# stm32f4discovery-daugherboard-v1.net
KiCad netlist of a schematic drawn in EAGLE
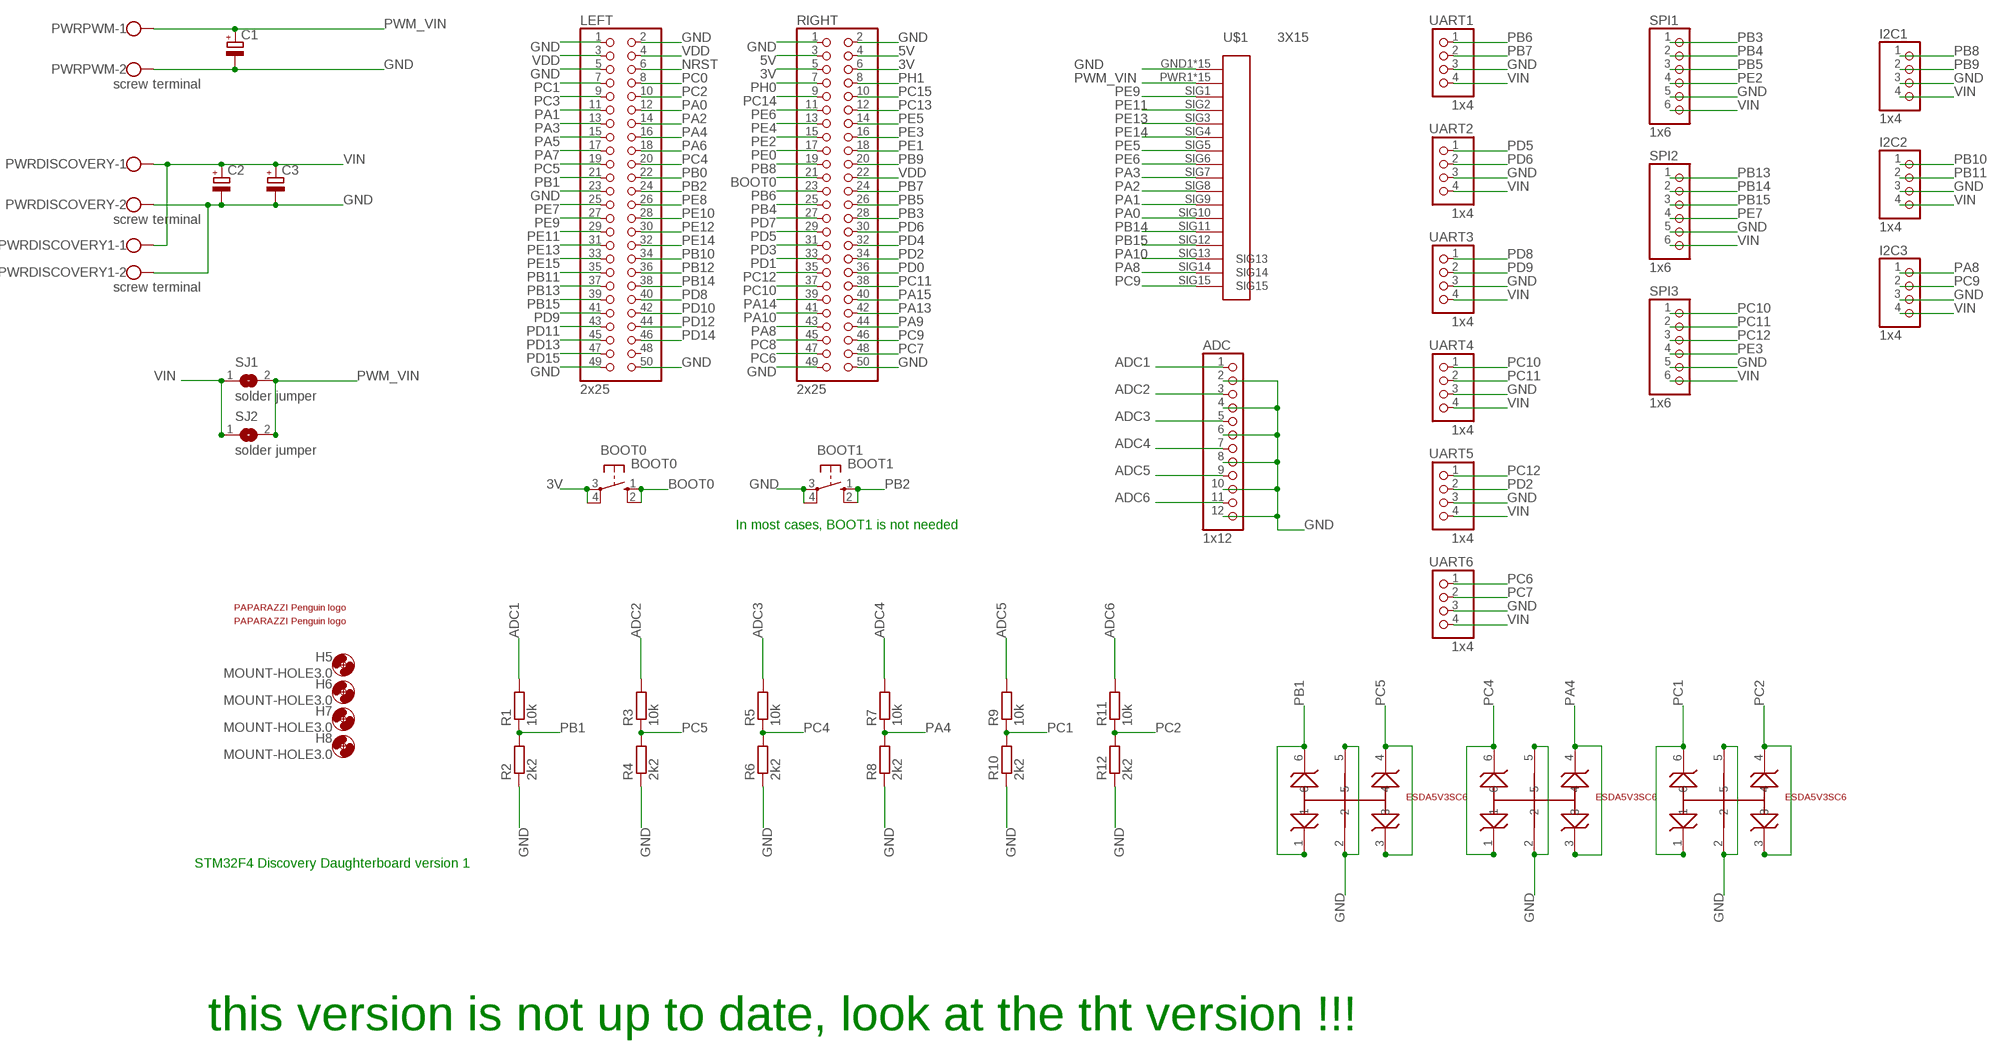
[diagram p0: schematic, sheet 1]

(export (version "E")
  (design (tool "Eeschema 10.0.6"))
  (components
    (comp (ref "ADC")
      (value "1x12")
      (footprint "eagle-import:1X12_90")
      (libsource (lib "eagle-import") (part "PINHD-1X12/90"))
    )
    (comp (ref "BOOT0")
      (value "BOOT0")
      (footprint "eagle-import:B3F-10XX")
      (fields (field (name "MPN") "B3F-1000"))
      (libsource (lib "eagle-import") (part "10-XX"))
    )
    (comp (ref "BOOT1")
      (value "BOOT1")
      (footprint "eagle-import:B3F-10XX")
      (fields (field (name "MPN") "B3F-1000"))
      (libsource (lib "eagle-import") (part "10-XX"))
    )
    (comp (ref "C1")
      (value "CPOL-EU153CLV-0807")
      (footprint "eagle-import:153CLV-0807")
      (libsource (lib "eagle-import") (part "CPOL-EU153CLV-0807"))
    )
    (comp (ref "C2")
      (value "CPOL-EU153CLV-0807")
      (footprint "eagle-import:153CLV-0807")
      (libsource (lib "eagle-import") (part "CPOL-EU153CLV-0807"))
    )
    (comp (ref "C3")
      (value "CPOL-EU153CLV-0807")
      (footprint "eagle-import:153CLV-0807")
      (libsource (lib "eagle-import") (part "CPOL-EU153CLV-0807"))
    )
    (comp (ref "H5")
      (value "MOUNT-HOLE3.0")
      (footprint "eagle-import:3,0")
      (libsource (lib "eagle-import") (part "MOUNT-HOLE3.0"))
    )
    (comp (ref "H6")
      (value "MOUNT-HOLE3.0")
      (footprint "eagle-import:3,0")
      (libsource (lib "eagle-import") (part "MOUNT-HOLE3.0"))
    )
    (comp (ref "H7")
      (value "MOUNT-HOLE3.0")
      (footprint "eagle-import:3,0")
      (libsource (lib "eagle-import") (part "MOUNT-HOLE3.0"))
    )
    (comp (ref "H8")
      (value "MOUNT-HOLE3.0")
      (footprint "eagle-import:3,0")
      (libsource (lib "eagle-import") (part "MOUNT-HOLE3.0"))
    )
    (comp (ref "I2C1")
      (value "1x4")
      (footprint "eagle-import:1X04_90")
      (libsource (lib "eagle-import") (part "PINHD-1X4/90"))
    )
    (comp (ref "I2C2")
      (value "1x4")
      (footprint "eagle-import:1X04_90")
      (libsource (lib "eagle-import") (part "PINHD-1X4/90"))
    )
    (comp (ref "I2C3")
      (value "1x4")
      (footprint "eagle-import:1X04_90")
      (libsource (lib "eagle-import") (part "PINHD-1X4/90"))
    )
    (comp (ref "LEFT")
      (value "2x25")
      (footprint "eagle-import:2X25")
      (libsource (lib "eagle-import") (part "PINHD-2X25"))
    )
    (comp (ref "PWRDISCOVERY")
      (value "screw terminal")
      (footprint "eagle-import:W237-102")
      (fields (field (name "MPN") "237-102"))
      (libsource (lib "eagle-import") (part "W237-102"))
    )
    (comp (ref "PWRDISCOVERY1")
      (value "screw terminal")
      (footprint "eagle-import:W237-102")
      (fields
        (field (name "MPN") "237-102")
        (field (name "MPN_1") "237-102")
        (field (name "OC_FARNELL") "unknown")
        (field (name "OC_NEWARK") "70K9898")
      )
      (libsource (lib "eagle-import") (part "W237-102"))
    )
    (comp (ref "PWRPWM")
      (value "screw terminal")
      (footprint "eagle-import:W237-102")
      (fields (field (name "MPN") "237-102"))
      (libsource (lib "eagle-import") (part "W237-102"))
    )
    (comp (ref "R1")
      (value "10k")
      (footprint "eagle-import:R0805")
      (libsource (lib "eagle-import") (part "R-EU_R0805"))
    )
    (comp (ref "R2")
      (value "2k2")
      (footprint "eagle-import:R0805")
      (libsource (lib "eagle-import") (part "R-EU_R0805"))
    )
    (comp (ref "R3")
      (value "10k")
      (footprint "eagle-import:R0805")
      (libsource (lib "eagle-import") (part "R-EU_R0805"))
    )
    (comp (ref "R4")
      (value "2k2")
      (footprint "eagle-import:R0805")
      (libsource (lib "eagle-import") (part "R-EU_R0805"))
    )
    (comp (ref "R5")
      (value "10k")
      (footprint "eagle-import:R0805")
      (libsource (lib "eagle-import") (part "R-EU_R0805"))
    )
    (comp (ref "R6")
      (value "2k2")
      (footprint "eagle-import:R0805")
      (libsource (lib "eagle-import") (part "R-EU_R0805"))
    )
    (comp (ref "R7")
      (value "10k")
      (footprint "eagle-import:R0805")
      (libsource (lib "eagle-import") (part "R-EU_R0805"))
    )
    (comp (ref "R8")
      (value "2k2")
      (footprint "eagle-import:R0805")
      (libsource (lib "eagle-import") (part "R-EU_R0805"))
    )
    (comp (ref "R9")
      (value "10k")
      (footprint "eagle-import:R0805")
      (libsource (lib "eagle-import") (part "R-EU_R0805"))
    )
    (comp (ref "R10")
      (value "2k2")
      (footprint "eagle-import:R0805")
      (libsource (lib "eagle-import") (part "R-EU_R0805"))
    )
    (comp (ref "R11")
      (value "10k")
      (footprint "eagle-import:R0805")
      (libsource (lib "eagle-import") (part "R-EU_R0805"))
    )
    (comp (ref "R12")
      (value "2k2")
      (footprint "eagle-import:R0805")
      (libsource (lib "eagle-import") (part "R-EU_R0805"))
    )
    (comp (ref "RIGHT")
      (value "2x25")
      (footprint "eagle-import:2X25")
      (libsource (lib "eagle-import") (part "PINHD-2X25"))
    )
    (comp (ref "SJ1")
      (value "solder jumper")
      (footprint "eagle-import:SJW")
      (libsource (lib "eagle-import") (part "SJW"))
    )
    (comp (ref "SJ2")
      (value "solder jumper")
      (footprint "eagle-import:SJW")
      (libsource (lib "eagle-import") (part "SJW"))
    )
    (comp (ref "SPI1")
      (value "1x6")
      (footprint "eagle-import:1X06_90")
      (libsource (lib "eagle-import") (part "PINHD-1X6/90"))
    )
    (comp (ref "SPI2")
      (value "1x6")
      (footprint "eagle-import:1X06_90")
      (libsource (lib "eagle-import") (part "PINHD-1X6/90"))
    )
    (comp (ref "SPI3")
      (value "1x6")
      (footprint "eagle-import:1X06_90")
      (libsource (lib "eagle-import") (part "PINHD-1X6/90"))
    )
    (comp (ref "U$1")
      (value "3X15")
      (footprint "eagle-import:3X15")
      (libsource (lib "eagle-import") (part "3X15"))
    )
    (comp (ref "U$2")
      (value "PAPARAZZI")
      (footprint "eagle-import:PAPARAZZI")
      (libsource (lib "eagle-import") (part "PAPARAZZI"))
    )
    (comp (ref "U$3")
      (value "PAPARAZZI")
      (footprint "eagle-import:PAPARAZZI")
      (libsource (lib "eagle-import") (part "PAPARAZZI"))
    )
    (comp (ref "U$4")
      (value "ESDA5V3SC6")
      (footprint "eagle-import:SOT23-6")
      (libsource (lib "eagle-import") (part "ESDA5V3SC6"))
    )
    (comp (ref "U$5")
      (value "ESDA5V3SC6")
      (footprint "eagle-import:SOT23-6")
      (libsource (lib "eagle-import") (part "ESDA5V3SC6"))
    )
    (comp (ref "U$6")
      (value "ESDA5V3SC6")
      (footprint "eagle-import:SOT23-6")
      (libsource (lib "eagle-import") (part "ESDA5V3SC6"))
    )
    (comp (ref "UART1")
      (value "1x4")
      (footprint "eagle-import:1X04_90")
      (libsource (lib "eagle-import") (part "PINHD-1X4/90"))
    )
    (comp (ref "UART2")
      (value "1x4")
      (footprint "eagle-import:1X04_90")
      (libsource (lib "eagle-import") (part "PINHD-1X4/90"))
    )
    (comp (ref "UART3")
      (value "1x4")
      (footprint "eagle-import:1X04_90")
      (libsource (lib "eagle-import") (part "PINHD-1X4/90"))
    )
    (comp (ref "UART4")
      (value "1x4")
      (footprint "eagle-import:1X04_90")
      (libsource (lib "eagle-import") (part "PINHD-1X4/90"))
    )
    (comp (ref "UART5")
      (value "1x4")
      (footprint "eagle-import:1X04_90")
      (libsource (lib "eagle-import") (part "PINHD-1X4/90"))
    )
    (comp (ref "UART6")
      (value "1x4")
      (footprint "eagle-import:1X04_90")
      (libsource (lib "eagle-import") (part "PINHD-1X4/90"))
    )
  )
  (nets
    (net (code "1") (name "/3V") (class "Default")
      (node (ref "BOOT0") (pin "3") (pinfunction "P_3") (pintype "passive"))
      (node (ref "BOOT0") (pin "4") (pinfunction "P1_4") (pintype "passive"))
      (node (ref "RIGHT") (pin "5") (pinfunction "5_5") (pintype "passive"))
      (node (ref "RIGHT") (pin "6") (pinfunction "6_6") (pintype "passive"))
    )
    (net (code "2") (name "/5V") (class "Default")
      (node (ref "RIGHT") (pin "3") (pinfunction "3_3") (pintype "passive"))
      (node (ref "RIGHT") (pin "4") (pinfunction "4_4") (pintype "passive"))
    )
    (net (code "3") (name "/ADC1") (class "Default")
      (node (ref "ADC") (pin "1") (pinfunction "1_1") (pintype "passive"))
      (node (ref "R1") (pin "2") (pinfunction "2_2") (pintype "passive"))
    )
    (net (code "4") (name "/ADC2") (class "Default")
      (node (ref "ADC") (pin "3") (pinfunction "3_3") (pintype "passive"))
      (node (ref "R3") (pin "2") (pinfunction "2_2") (pintype "passive"))
    )
    (net (code "5") (name "/ADC3") (class "Default")
      (node (ref "ADC") (pin "5") (pinfunction "5_5") (pintype "passive"))
      (node (ref "R5") (pin "2") (pinfunction "2_2") (pintype "passive"))
    )
    (net (code "6") (name "/ADC4") (class "Default")
      (node (ref "ADC") (pin "7") (pinfunction "7_7") (pintype "passive"))
      (node (ref "R7") (pin "2") (pinfunction "2_2") (pintype "passive"))
    )
    (net (code "7") (name "/ADC5") (class "Default")
      (node (ref "ADC") (pin "9") (pinfunction "9_9") (pintype "passive"))
      (node (ref "R9") (pin "2") (pinfunction "2_2") (pintype "passive"))
    )
    (net (code "8") (name "/ADC6") (class "Default")
      (node (ref "ADC") (pin "11") (pinfunction "11_11") (pintype "passive"))
      (node (ref "R11") (pin "2") (pinfunction "2_2") (pintype "passive"))
    )
    (net (code "9") (name "/BOOT0") (class "Default")
      (node (ref "BOOT0") (pin "1") (pinfunction "S_1") (pintype "passive"))
      (node (ref "BOOT0") (pin "2") (pinfunction "S1_2") (pintype "passive"))
      (node (ref "RIGHT") (pin "21") (pinfunction "21_21") (pintype "passive"))
    )
    (net (code "10") (name "/GND") (class "Default")
      (node (ref "ADC") (pin "10") (pinfunction "10_10") (pintype "passive"))
      (node (ref "ADC") (pin "12") (pinfunction "12_12") (pintype "passive"))
      (node (ref "ADC") (pin "2") (pinfunction "2_2") (pintype "passive"))
      (node (ref "ADC") (pin "4") (pinfunction "4_4") (pintype "passive"))
      (node (ref "ADC") (pin "6") (pinfunction "6_6") (pintype "passive"))
      (node (ref "ADC") (pin "8") (pinfunction "8_8") (pintype "passive"))
      (node (ref "BOOT1") (pin "3") (pinfunction "P_3") (pintype "passive"))
      (node (ref "BOOT1") (pin "4") (pinfunction "P1_4") (pintype "passive"))
      (node (ref "C1") (pin "-") (pinfunction "-_-") (pintype "passive"))
      (node (ref "C2") (pin "-") (pinfunction "-_-") (pintype "passive"))
      (node (ref "C3") (pin "-") (pinfunction "-_-") (pintype "passive"))
      (node (ref "I2C1") (pin "3") (pinfunction "3_3") (pintype "passive"))
      (node (ref "I2C2") (pin "3") (pinfunction "3_3") (pintype "passive"))
      (node (ref "I2C3") (pin "3") (pinfunction "3_3") (pintype "passive"))
      (node (ref "LEFT") (pin "1") (pinfunction "1_1") (pintype "passive"))
      (node (ref "LEFT") (pin "2") (pinfunction "2_2") (pintype "passive"))
      (node (ref "LEFT") (pin "23") (pinfunction "23_23") (pintype "passive"))
      (node (ref "LEFT") (pin "49") (pinfunction "49_49") (pintype "passive"))
      (node (ref "LEFT") (pin "5") (pinfunction "5_5") (pintype "passive"))
      (node (ref "LEFT") (pin "50") (pinfunction "50_50") (pintype "passive"))
      (node (ref "PWRDISCOVERY") (pin "2") (pinfunction "KL_2") (pintype "passive"))
      (node (ref "PWRDISCOVERY1") (pin "2") (pinfunction "KL_2") (pintype "passive"))
      (node (ref "PWRPWM") (pin "2") (pinfunction "KL_2") (pintype "passive"))
      (node (ref "R10") (pin "1") (pinfunction "1_1") (pintype "passive"))
      (node (ref "R12") (pin "1") (pinfunction "1_1") (pintype "passive"))
      (node (ref "R2") (pin "1") (pinfunction "1_1") (pintype "passive"))
      (node (ref "R4") (pin "1") (pinfunction "1_1") (pintype "passive"))
      (node (ref "R6") (pin "1") (pinfunction "1_1") (pintype "passive"))
      (node (ref "R8") (pin "1") (pinfunction "1_1") (pintype "passive"))
      (node (ref "RIGHT") (pin "1") (pinfunction "1_1") (pintype "passive"))
      (node (ref "RIGHT") (pin "2") (pinfunction "2_2") (pintype "passive"))
      (node (ref "RIGHT") (pin "49") (pinfunction "49_49") (pintype "passive"))
      (node (ref "RIGHT") (pin "50") (pinfunction "50_50") (pintype "passive"))
      (node (ref "SPI1") (pin "5") (pinfunction "5_5") (pintype "passive"))
      (node (ref "SPI2") (pin "5") (pinfunction "5_5") (pintype "passive"))
      (node (ref "SPI3") (pin "5") (pinfunction "5_5") (pintype "passive"))
      (node (ref "U$1") (pin "GND1") (pinfunction "GND_GND1") (pintype "bidirectional"))
      (node (ref "U$1") (pin "GND10") (pinfunction "GND_GND10") (pintype "bidirectional"))
      (node (ref "U$1") (pin "GND11") (pinfunction "GND_GND11") (pintype "bidirectional"))
      (node (ref "U$1") (pin "GND12") (pinfunction "GND_GND12") (pintype "bidirectional"))
      (node (ref "U$1") (pin "GND13") (pinfunction "GND_GND13") (pintype "bidirectional"))
      (node (ref "U$1") (pin "GND14") (pinfunction "GND_GND14") (pintype "bidirectional"))
      (node (ref "U$1") (pin "GND15") (pinfunction "GND_GND15") (pintype "bidirectional"))
      (node (ref "U$1") (pin "GND2") (pinfunction "GND_GND2") (pintype "bidirectional"))
      (node (ref "U$1") (pin "GND3") (pinfunction "GND_GND3") (pintype "bidirectional"))
      (node (ref "U$1") (pin "GND4") (pinfunction "GND_GND4") (pintype "bidirectional"))
      (node (ref "U$1") (pin "GND5") (pinfunction "GND_GND5") (pintype "bidirectional"))
      (node (ref "U$1") (pin "GND6") (pinfunction "GND_GND6") (pintype "bidirectional"))
      (node (ref "U$1") (pin "GND7") (pinfunction "GND_GND7") (pintype "bidirectional"))
      (node (ref "U$1") (pin "GND8") (pinfunction "GND_GND8") (pintype "bidirectional"))
      (node (ref "U$1") (pin "GND9") (pinfunction "GND_GND9") (pintype "bidirectional"))
      (node (ref "U$4") (pin "2") (pinfunction "2_2") (pintype "bidirectional"))
      (node (ref "U$4") (pin "5") (pinfunction "5_5") (pintype "bidirectional"))
      (node (ref "U$5") (pin "2") (pinfunction "2_2") (pintype "bidirectional"))
      (node (ref "U$5") (pin "5") (pinfunction "5_5") (pintype "bidirectional"))
      (node (ref "U$6") (pin "2") (pinfunction "2_2") (pintype "bidirectional"))
      (node (ref "U$6") (pin "5") (pinfunction "5_5") (pintype "bidirectional"))
      (node (ref "UART1") (pin "3") (pinfunction "3_3") (pintype "passive"))
      (node (ref "UART2") (pin "3") (pinfunction "3_3") (pintype "passive"))
      (node (ref "UART3") (pin "3") (pinfunction "3_3") (pintype "passive"))
      (node (ref "UART4") (pin "3") (pinfunction "3_3") (pintype "passive"))
      (node (ref "UART5") (pin "3") (pinfunction "3_3") (pintype "passive"))
      (node (ref "UART6") (pin "3") (pinfunction "3_3") (pintype "passive"))
    )
    (net (code "11") (name "/NRST") (class "Default")
      (node (ref "LEFT") (pin "6") (pinfunction "6_6") (pintype "passive"))
    )
    (net (code "12") (name "/PA0") (class "Default")
      (node (ref "LEFT") (pin "12") (pinfunction "12_12") (pintype "passive"))
      (node (ref "U$1") (pin "SIG10") (pinfunction "SIG10_SIG10") (pintype "bidirectional"))
    )
    (net (code "13") (name "/PA1") (class "Default")
      (node (ref "LEFT") (pin "11") (pinfunction "11_11") (pintype "passive"))
      (node (ref "U$1") (pin "SIG9") (pinfunction "SIG9_SIG9") (pintype "bidirectional"))
    )
    (net (code "14") (name "/PA2") (class "Default")
      (node (ref "LEFT") (pin "14") (pinfunction "14_14") (pintype "passive"))
      (node (ref "U$1") (pin "SIG8") (pinfunction "SIG8_SIG8") (pintype "bidirectional"))
    )
    (net (code "15") (name "/PA3") (class "Default")
      (node (ref "LEFT") (pin "13") (pinfunction "13_13") (pintype "passive"))
      (node (ref "U$1") (pin "SIG7") (pinfunction "SIG7_SIG7") (pintype "bidirectional"))
    )
    (net (code "16") (name "/PA4") (class "Default")
      (node (ref "LEFT") (pin "16") (pinfunction "16_16") (pintype "passive"))
      (node (ref "R7") (pin "1") (pinfunction "1_1") (pintype "passive"))
      (node (ref "R8") (pin "2") (pinfunction "2_2") (pintype "passive"))
      (node (ref "U$5") (pin "3") (pinfunction "3_3") (pintype "bidirectional"))
      (node (ref "U$5") (pin "4") (pinfunction "4_4") (pintype "bidirectional"))
    )
    (net (code "17") (name "/PA5") (class "Default")
      (node (ref "LEFT") (pin "15") (pinfunction "15_15") (pintype "passive"))
    )
    (net (code "18") (name "/PA6") (class "Default")
      (node (ref "LEFT") (pin "18") (pinfunction "18_18") (pintype "passive"))
    )
    (net (code "19") (name "/PA7") (class "Default")
      (node (ref "LEFT") (pin "17") (pinfunction "17_17") (pintype "passive"))
    )
    (net (code "20") (name "/PA8") (class "Default")
      (node (ref "I2C3") (pin "1") (pinfunction "1_1") (pintype "passive"))
      (node (ref "RIGHT") (pin "43") (pinfunction "43_43") (pintype "passive"))
      (node (ref "U$1") (pin "SIG14") (pinfunction "SIG14_SIG14") (pintype "bidirectional"))
    )
    (net (code "21") (name "/PA9") (class "Default")
      (node (ref "RIGHT") (pin "44") (pinfunction "44_44") (pintype "passive"))
    )
    (net (code "22") (name "/PA10") (class "Default")
      (node (ref "RIGHT") (pin "41") (pinfunction "41_41") (pintype "passive"))
      (node (ref "U$1") (pin "SIG13") (pinfunction "SIG13_SIG13") (pintype "bidirectional"))
    )
    (net (code "23") (name "/PA13") (class "Default")
      (node (ref "RIGHT") (pin "42") (pinfunction "42_42") (pintype "passive"))
    )
    (net (code "24") (name "/PA14") (class "Default")
      (node (ref "RIGHT") (pin "39") (pinfunction "39_39") (pintype "passive"))
    )
    (net (code "25") (name "/PA15") (class "Default")
      (node (ref "RIGHT") (pin "40") (pinfunction "40_40") (pintype "passive"))
    )
    (net (code "26") (name "/PB0") (class "Default")
      (node (ref "LEFT") (pin "22") (pinfunction "22_22") (pintype "passive"))
    )
    (net (code "27") (name "/PB1") (class "Default")
      (node (ref "LEFT") (pin "21") (pinfunction "21_21") (pintype "passive"))
      (node (ref "R1") (pin "1") (pinfunction "1_1") (pintype "passive"))
      (node (ref "R2") (pin "2") (pinfunction "2_2") (pintype "passive"))
      (node (ref "U$4") (pin "1") (pinfunction "1_1") (pintype "bidirectional"))
      (node (ref "U$4") (pin "6") (pinfunction "6_6") (pintype "bidirectional"))
    )
    (net (code "28") (name "/PB2") (class "Default")
      (node (ref "BOOT1") (pin "1") (pinfunction "S_1") (pintype "passive"))
      (node (ref "BOOT1") (pin "2") (pinfunction "S1_2") (pintype "passive"))
      (node (ref "LEFT") (pin "24") (pinfunction "24_24") (pintype "passive"))
    )
    (net (code "29") (name "/PB3") (class "Default")
      (node (ref "RIGHT") (pin "28") (pinfunction "28_28") (pintype "passive"))
      (node (ref "SPI1") (pin "1") (pinfunction "1_1") (pintype "passive"))
    )
    (net (code "30") (name "/PB4") (class "Default")
      (node (ref "RIGHT") (pin "25") (pinfunction "25_25") (pintype "passive"))
      (node (ref "SPI1") (pin "2") (pinfunction "2_2") (pintype "passive"))
    )
    (net (code "31") (name "/PB5") (class "Default")
      (node (ref "RIGHT") (pin "26") (pinfunction "26_26") (pintype "passive"))
      (node (ref "SPI1") (pin "3") (pinfunction "3_3") (pintype "passive"))
    )
    (net (code "32") (name "/PB6") (class "Default")
      (node (ref "RIGHT") (pin "23") (pinfunction "23_23") (pintype "passive"))
      (node (ref "UART1") (pin "1") (pinfunction "1_1") (pintype "passive"))
    )
    (net (code "33") (name "/PB7") (class "Default")
      (node (ref "RIGHT") (pin "24") (pinfunction "24_24") (pintype "passive"))
      (node (ref "UART1") (pin "2") (pinfunction "2_2") (pintype "passive"))
    )
    (net (code "34") (name "/PB8") (class "Default")
      (node (ref "I2C1") (pin "1") (pinfunction "1_1") (pintype "passive"))
      (node (ref "RIGHT") (pin "19") (pinfunction "19_19") (pintype "passive"))
    )
    (net (code "35") (name "/PB9") (class "Default")
      (node (ref "I2C1") (pin "2") (pinfunction "2_2") (pintype "passive"))
      (node (ref "RIGHT") (pin "20") (pinfunction "20_20") (pintype "passive"))
    )
    (net (code "36") (name "/PB10") (class "Default")
      (node (ref "I2C2") (pin "1") (pinfunction "1_1") (pintype "passive"))
      (node (ref "LEFT") (pin "34") (pinfunction "34_34") (pintype "passive"))
    )
    (net (code "37") (name "/PB11") (class "Default")
      (node (ref "I2C2") (pin "2") (pinfunction "2_2") (pintype "passive"))
      (node (ref "LEFT") (pin "35") (pinfunction "35_35") (pintype "passive"))
    )
    (net (code "38") (name "/PB12") (class "Default")
      (node (ref "LEFT") (pin "36") (pinfunction "36_36") (pintype "passive"))
    )
    (net (code "39") (name "/PB13") (class "Default")
      (node (ref "LEFT") (pin "37") (pinfunction "37_37") (pintype "passive"))
      (node (ref "SPI2") (pin "1") (pinfunction "1_1") (pintype "passive"))
    )
    (net (code "40") (name "/PB14") (class "Default")
      (node (ref "LEFT") (pin "38") (pinfunction "38_38") (pintype "passive"))
      (node (ref "SPI2") (pin "2") (pinfunction "2_2") (pintype "passive"))
      (node (ref "U$1") (pin "SIG11") (pinfunction "SIG11_SIG11") (pintype "bidirectional"))
    )
    (net (code "41") (name "/PB15") (class "Default")
      (node (ref "LEFT") (pin "39") (pinfunction "39_39") (pintype "passive"))
      (node (ref "SPI2") (pin "3") (pinfunction "3_3") (pintype "passive"))
      (node (ref "U$1") (pin "SIG12") (pinfunction "SIG12_SIG12") (pintype "bidirectional"))
    )
    (net (code "42") (name "/PC0") (class "Default")
      (node (ref "LEFT") (pin "8") (pinfunction "8_8") (pintype "passive"))
    )
    (net (code "43") (name "/PC1") (class "Default")
      (node (ref "LEFT") (pin "7") (pinfunction "7_7") (pintype "passive"))
      (node (ref "R10") (pin "2") (pinfunction "2_2") (pintype "passive"))
      (node (ref "R9") (pin "1") (pinfunction "1_1") (pintype "passive"))
      (node (ref "U$6") (pin "1") (pinfunction "1_1") (pintype "bidirectional"))
      (node (ref "U$6") (pin "6") (pinfunction "6_6") (pintype "bidirectional"))
    )
    (net (code "44") (name "/PC2") (class "Default")
      (node (ref "LEFT") (pin "10") (pinfunction "10_10") (pintype "passive"))
      (node (ref "R11") (pin "1") (pinfunction "1_1") (pintype "passive"))
      (node (ref "R12") (pin "2") (pinfunction "2_2") (pintype "passive"))
      (node (ref "U$6") (pin "3") (pinfunction "3_3") (pintype "bidirectional"))
      (node (ref "U$6") (pin "4") (pinfunction "4_4") (pintype "bidirectional"))
    )
    (net (code "45") (name "/PC3") (class "Default")
      (node (ref "LEFT") (pin "9") (pinfunction "9_9") (pintype "passive"))
    )
    (net (code "46") (name "/PC4") (class "Default")
      (node (ref "LEFT") (pin "20") (pinfunction "20_20") (pintype "passive"))
      (node (ref "R5") (pin "1") (pinfunction "1_1") (pintype "passive"))
      (node (ref "R6") (pin "2") (pinfunction "2_2") (pintype "passive"))
      (node (ref "U$5") (pin "1") (pinfunction "1_1") (pintype "bidirectional"))
      (node (ref "U$5") (pin "6") (pinfunction "6_6") (pintype "bidirectional"))
    )
    (net (code "47") (name "/PC5") (class "Default")
      (node (ref "LEFT") (pin "19") (pinfunction "19_19") (pintype "passive"))
      (node (ref "R3") (pin "1") (pinfunction "1_1") (pintype "passive"))
      (node (ref "R4") (pin "2") (pinfunction "2_2") (pintype "passive"))
      (node (ref "U$4") (pin "3") (pinfunction "3_3") (pintype "bidirectional"))
      (node (ref "U$4") (pin "4") (pinfunction "4_4") (pintype "bidirectional"))
    )
    (net (code "48") (name "/PC6") (class "Default")
      (node (ref "RIGHT") (pin "47") (pinfunction "47_47") (pintype "passive"))
      (node (ref "UART6") (pin "1") (pinfunction "1_1") (pintype "passive"))
    )
    (net (code "49") (name "/PC7") (class "Default")
      (node (ref "RIGHT") (pin "48") (pinfunction "48_48") (pintype "passive"))
      (node (ref "UART6") (pin "2") (pinfunction "2_2") (pintype "passive"))
    )
    (net (code "50") (name "/PC8") (class "Default")
      (node (ref "RIGHT") (pin "45") (pinfunction "45_45") (pintype "passive"))
    )
    (net (code "51") (name "/PC9") (class "Default")
      (node (ref "I2C3") (pin "2") (pinfunction "2_2") (pintype "passive"))
      (node (ref "RIGHT") (pin "46") (pinfunction "46_46") (pintype "passive"))
      (node (ref "U$1") (pin "SIG15") (pinfunction "SIG15_SIG15") (pintype "bidirectional"))
    )
    (net (code "52") (name "/PC10") (class "Default")
      (node (ref "RIGHT") (pin "37") (pinfunction "37_37") (pintype "passive"))
      (node (ref "SPI3") (pin "1") (pinfunction "1_1") (pintype "passive"))
      (node (ref "UART4") (pin "1") (pinfunction "1_1") (pintype "passive"))
    )
    (net (code "53") (name "/PC11") (class "Default")
      (node (ref "RIGHT") (pin "38") (pinfunction "38_38") (pintype "passive"))
      (node (ref "SPI3") (pin "2") (pinfunction "2_2") (pintype "passive"))
      (node (ref "UART4") (pin "2") (pinfunction "2_2") (pintype "passive"))
    )
    (net (code "54") (name "/PC12") (class "Default")
      (node (ref "RIGHT") (pin "35") (pinfunction "35_35") (pintype "passive"))
      (node (ref "SPI3") (pin "3") (pinfunction "3_3") (pintype "passive"))
      (node (ref "UART5") (pin "1") (pinfunction "1_1") (pintype "passive"))
    )
    (net (code "55") (name "/PC13") (class "Default")
      (node (ref "RIGHT") (pin "12") (pinfunction "12_12") (pintype "passive"))
    )
    (net (code "56") (name "/PC14") (class "Default")
      (node (ref "RIGHT") (pin "9") (pinfunction "9_9") (pintype "passive"))
    )
    (net (code "57") (name "/PC15") (class "Default")
      (node (ref "RIGHT") (pin "10") (pinfunction "10_10") (pintype "passive"))
    )
    (net (code "58") (name "/PD0") (class "Default")
      (node (ref "RIGHT") (pin "36") (pinfunction "36_36") (pintype "passive"))
    )
    (net (code "59") (name "/PD1") (class "Default")
      (node (ref "RIGHT") (pin "33") (pinfunction "33_33") (pintype "passive"))
    )
    (net (code "60") (name "/PD2") (class "Default")
      (node (ref "RIGHT") (pin "34") (pinfunction "34_34") (pintype "passive"))
      (node (ref "UART5") (pin "2") (pinfunction "2_2") (pintype "passive"))
    )
    (net (code "61") (name "/PD3") (class "Default")
      (node (ref "RIGHT") (pin "31") (pinfunction "31_31") (pintype "passive"))
    )
    (net (code "62") (name "/PD4") (class "Default")
      (node (ref "RIGHT") (pin "32") (pinfunction "32_32") (pintype "passive"))
    )
    (net (code "63") (name "/PD5") (class "Default")
      (node (ref "RIGHT") (pin "29") (pinfunction "29_29") (pintype "passive"))
      (node (ref "UART2") (pin "1") (pinfunction "1_1") (pintype "passive"))
    )
    (net (code "64") (name "/PD6") (class "Default")
      (node (ref "RIGHT") (pin "30") (pinfunction "30_30") (pintype "passive"))
      (node (ref "UART2") (pin "2") (pinfunction "2_2") (pintype "passive"))
    )
    (net (code "65") (name "/PD7") (class "Default")
      (node (ref "RIGHT") (pin "27") (pinfunction "27_27") (pintype "passive"))
    )
    (net (code "66") (name "/PD8") (class "Default")
      (node (ref "LEFT") (pin "40") (pinfunction "40_40") (pintype "passive"))
      (node (ref "UART3") (pin "1") (pinfunction "1_1") (pintype "passive"))
    )
    (net (code "67") (name "/PD9") (class "Default")
      (node (ref "LEFT") (pin "41") (pinfunction "41_41") (pintype "passive"))
      (node (ref "UART3") (pin "2") (pinfunction "2_2") (pintype "passive"))
    )
    (net (code "68") (name "/PD10") (class "Default")
      (node (ref "LEFT") (pin "42") (pinfunction "42_42") (pintype "passive"))
    )
    (net (code "69") (name "/PD11") (class "Default")
      (node (ref "LEFT") (pin "43") (pinfunction "43_43") (pintype "passive"))
    )
    (net (code "70") (name "/PD12") (class "Default")
      (node (ref "LEFT") (pin "44") (pinfunction "44_44") (pintype "passive"))
    )
    (net (code "71") (name "/PD13") (class "Default")
      (node (ref "LEFT") (pin "45") (pinfunction "45_45") (pintype "passive"))
    )
    (net (code "72") (name "/PD14") (class "Default")
      (node (ref "LEFT") (pin "46") (pinfunction "46_46") (pintype "passive"))
    )
    (net (code "73") (name "/PD15") (class "Default")
      (node (ref "LEFT") (pin "47") (pinfunction "47_47") (pintype "passive"))
    )
    (net (code "74") (name "/PE0") (class "Default")
      (node (ref "RIGHT") (pin "17") (pinfunction "17_17") (pintype "passive"))
    )
    (net (code "75") (name "/PE1") (class "Default")
      (node (ref "RIGHT") (pin "18") (pinfunction "18_18") (pintype "passive"))
    )
    (net (code "76") (name "/PE2") (class "Default")
      (node (ref "RIGHT") (pin "15") (pinfunction "15_15") (pintype "passive"))
      (node (ref "SPI1") (pin "4") (pinfunction "4_4") (pintype "passive"))
    )
    (net (code "77") (name "/PE3") (class "Default")
      (node (ref "RIGHT") (pin "16") (pinfunction "16_16") (pintype "passive"))
      (node (ref "SPI3") (pin "4") (pinfunction "4_4") (pintype "passive"))
    )
    (net (code "78") (name "/PE4") (class "Default")
      (node (ref "RIGHT") (pin "13") (pinfunction "13_13") (pintype "passive"))
    )
    (net (code "79") (name "/PE5") (class "Default")
      (node (ref "RIGHT") (pin "14") (pinfunction "14_14") (pintype "passive"))
      (node (ref "U$1") (pin "SIG5") (pinfunction "SIG5_SIG5") (pintype "bidirectional"))
    )
    (net (code "80") (name "/PE6") (class "Default")
      (node (ref "RIGHT") (pin "11") (pinfunction "11_11") (pintype "passive"))
      (node (ref "U$1") (pin "SIG6") (pinfunction "SIG6_SIG6") (pintype "bidirectional"))
    )
    (net (code "81") (name "/PE7") (class "Default")
      (node (ref "LEFT") (pin "25") (pinfunction "25_25") (pintype "passive"))
      (node (ref "SPI2") (pin "4") (pinfunction "4_4") (pintype "passive"))
    )
    (net (code "82") (name "/PE8") (class "Default")
      (node (ref "LEFT") (pin "26") (pinfunction "26_26") (pintype "passive"))
    )
    (net (code "83") (name "/PE9") (class "Default")
      (node (ref "LEFT") (pin "27") (pinfunction "27_27") (pintype "passive"))
      (node (ref "U$1") (pin "SIG1") (pinfunction "SIG1_SIG1") (pintype "bidirectional"))
    )
    (net (code "84") (name "/PE10") (class "Default")
      (node (ref "LEFT") (pin "28") (pinfunction "28_28") (pintype "passive"))
    )
    (net (code "85") (name "/PE11") (class "Default")
      (node (ref "LEFT") (pin "29") (pinfunction "29_29") (pintype "passive"))
      (node (ref "U$1") (pin "SIG2") (pinfunction "SIG2_SIG2") (pintype "bidirectional"))
    )
    (net (code "86") (name "/PE12") (class "Default")
      (node (ref "LEFT") (pin "30") (pinfunction "30_30") (pintype "passive"))
    )
    (net (code "87") (name "/PE13") (class "Default")
      (node (ref "LEFT") (pin "31") (pinfunction "31_31") (pintype "passive"))
      (node (ref "U$1") (pin "SIG3") (pinfunction "SIG3_SIG3") (pintype "bidirectional"))
    )
    (net (code "88") (name "/PE14") (class "Default")
      (node (ref "LEFT") (pin "32") (pinfunction "32_32") (pintype "passive"))
      (node (ref "U$1") (pin "SIG4") (pinfunction "SIG4_SIG4") (pintype "bidirectional"))
    )
    (net (code "89") (name "/PE15") (class "Default")
      (node (ref "LEFT") (pin "33") (pinfunction "33_33") (pintype "passive"))
    )
    (net (code "90") (name "/PH0") (class "Default")
      (node (ref "RIGHT") (pin "7") (pinfunction "7_7") (pintype "passive"))
    )
    (net (code "91") (name "/PH1") (class "Default")
      (node (ref "RIGHT") (pin "8") (pinfunction "8_8") (pintype "passive"))
    )
    (net (code "92") (name "/PWM_VIN") (class "Default")
      (node (ref "C1") (pin "+") (pinfunction "+_+") (pintype "passive"))
      (node (ref "PWRPWM") (pin "1") (pinfunction "KL_1") (pintype "passive"))
      (node (ref "SJ1") (pin "2") (pinfunction "2_2") (pintype "passive"))
      (node (ref "SJ2") (pin "2") (pinfunction "2_2") (pintype "passive"))
      (node (ref "U$1") (pin "PWR1") (pinfunction "PWR_PWR1") (pintype "bidirectional"))
      (node (ref "U$1") (pin "PWR10") (pinfunction "PWR_PWR10") (pintype "bidirectional"))
      (node (ref "U$1") (pin "PWR11") (pinfunction "PWR_PWR11") (pintype "bidirectional"))
      (node (ref "U$1") (pin "PWR12") (pinfunction "PWR_PWR12") (pintype "bidirectional"))
      (node (ref "U$1") (pin "PWR13") (pinfunction "PWR_PWR13") (pintype "bidirectional"))
      (node (ref "U$1") (pin "PWR14") (pinfunction "PWR_PWR14") (pintype "bidirectional"))
      (node (ref "U$1") (pin "PWR15") (pinfunction "PWR_PWR15") (pintype "bidirectional"))
      (node (ref "U$1") (pin "PWR2") (pinfunction "PWR_PWR2") (pintype "bidirectional"))
      (node (ref "U$1") (pin "PWR3") (pinfunction "PWR_PWR3") (pintype "bidirectional"))
      (node (ref "U$1") (pin "PWR4") (pinfunction "PWR_PWR4") (pintype "bidirectional"))
      (node (ref "U$1") (pin "PWR5") (pinfunction "PWR_PWR5") (pintype "bidirectional"))
      (node (ref "U$1") (pin "PWR6") (pinfunction "PWR_PWR6") (pintype "bidirectional"))
      (node (ref "U$1") (pin "PWR7") (pinfunction "PWR_PWR7") (pintype "bidirectional"))
      (node (ref "U$1") (pin "PWR8") (pinfunction "PWR_PWR8") (pintype "bidirectional"))
      (node (ref "U$1") (pin "PWR9") (pinfunction "PWR_PWR9") (pintype "bidirectional"))
    )
    (net (code "93") (name "/VDD") (class "Default")
      (node (ref "LEFT") (pin "3") (pinfunction "3_3") (pintype "passive"))
      (node (ref "LEFT") (pin "4") (pinfunction "4_4") (pintype "passive"))
      (node (ref "RIGHT") (pin "22") (pinfunction "22_22") (pintype "passive"))
    )
    (net (code "94") (name "/VIN") (class "Default")
      (node (ref "C2") (pin "+") (pinfunction "+_+") (pintype "passive"))
      (node (ref "C3") (pin "+") (pinfunction "+_+") (pintype "passive"))
      (node (ref "I2C1") (pin "4") (pinfunction "4_4") (pintype "passive"))
      (node (ref "I2C2") (pin "4") (pinfunction "4_4") (pintype "passive"))
      (node (ref "I2C3") (pin "4") (pinfunction "4_4") (pintype "passive"))
      (node (ref "PWRDISCOVERY") (pin "1") (pinfunction "KL_1") (pintype "passive"))
      (node (ref "PWRDISCOVERY1") (pin "1") (pinfunction "KL_1") (pintype "passive"))
      (node (ref "SJ1") (pin "1") (pinfunction "1_1") (pintype "passive"))
      (node (ref "SJ2") (pin "1") (pinfunction "1_1") (pintype "passive"))
      (node (ref "SPI1") (pin "6") (pinfunction "6_6") (pintype "passive"))
      (node (ref "SPI2") (pin "6") (pinfunction "6_6") (pintype "passive"))
      (node (ref "SPI3") (pin "6") (pinfunction "6_6") (pintype "passive"))
      (node (ref "UART1") (pin "4") (pinfunction "4_4") (pintype "passive"))
      (node (ref "UART2") (pin "4") (pinfunction "4_4") (pintype "passive"))
      (node (ref "UART3") (pin "4") (pinfunction "4_4") (pintype "passive"))
      (node (ref "UART4") (pin "4") (pinfunction "4_4") (pintype "passive"))
      (node (ref "UART5") (pin "4") (pinfunction "4_4") (pintype "passive"))
      (node (ref "UART6") (pin "4") (pinfunction "4_4") (pintype "passive"))
    )
    (net (code "95") (name "unconnected-(LEFT-Pad48)") (class "Default")
      (node (ref "LEFT") (pin "48") (pinfunction "48_48") (pintype "passive"))
    )
  )
)
